# Power_3_3V_to_mc.net
KiCad netlist of a schematic drawn in Altium Designer
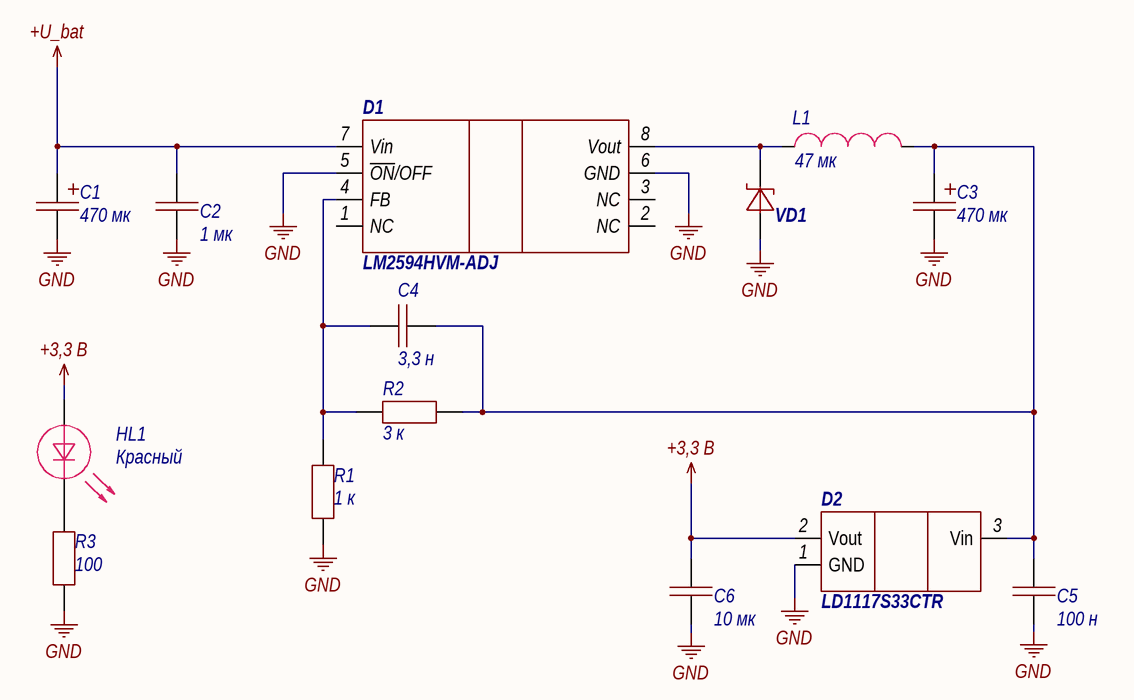
[diagram p0: Power 3.3V to mc.SchDoc]

(export (version "E")
  (design (tool "Eeschema 10.0.6"))
  (components
    (comp (ref "C1")
      (value "470 мк")
      (footprint "RADIAL-2 8mm")
      (description "Конденсатор электролит. 470 мкФ, 50 В, 8 мм")
      (fields (field (name "Comment") "Конденсатор полевой"))
      (libsource (lib "PionerSCHLibrary") (part "Capacitor_pol"))
    )
    (comp (ref "C2")
      (value "1 мк")
      (footprint "0603C")
      (description "Конденсатор керамический SMD, 0603, 1 мкФ")
      (fields (field (name "Comment") "Конденсатор"))
      (libsource (lib "PionerSCHLibrary") (part "Capacitor"))
    )
    (comp (ref "C3")
      (value "470 мк")
      (footprint "RADIAL-2 10MM")
      (description "Конденсатор электролит. 35В, 470мкФ, 10x16")
      (fields (field (name "Comment") "Конденсатор полевой"))
      (libsource (lib "PionerSCHLibrary") (part "Capacitor_pol"))
    )
    (comp (ref "C4")
      (value "3,3 н")
      (footprint "0603C")
      (description "Конденсатор керамический SMD, 0603")
      (fields (field (name "Comment") "Конденсатор"))
      (libsource (lib "PionerSCHLibrary") (part "Capacitor"))
    )
    (comp (ref "C5")
      (value "100 н")
      (footprint "0603C")
      (description "Конденсатор керамический SMD, 0603, 0.1 uF")
      (fields (field (name "Comment") "Конденсатор"))
      (libsource (lib "PionerSCHLibrary") (part "Capacitor"))
    )
    (comp (ref "C6")
      (value "10 мк")
      (footprint "0603C")
      (description "Конденсатор керамический smd 10 мкФ, 0603,")
      (fields (field (name "Comment") "Конденсатор"))
      (libsource (lib "PionerSCHLibrary") (part "Capacitor"))
    )
    (comp (ref "D1")
      (value "LM2594HVM-ADJ")
      (footprint "SOIC_8N")
      (description "Импульсный DC-DC преобразователь, вход до 60 вольт, регулируемый выход, выходной ток 2 Ампера")
      (libsource (lib "PionerSCHLibrary") (part "LM2594HVM-ADJ"))
    )
    (comp (ref "D2")
      (value "LD1117S33CTR")
      (footprint "SOT223")
      (libsource (lib "PionerSCHLibrary") (part "LD1117S33CTR"))
    )
    (comp (ref "HL1")
      (value "~")
      (footprint "0805D")
      (description "Светодиод SMD 0805, 30 мА, 2.1 В")
      (fields (field (name "COLOR") "Красный"))
      (libsource (lib "PionerSCHLibrary") (part "LED"))
    )
    (comp (ref "L1")
      (value "47 мк")
      (footprint "IND_B82477G")
      (description "Катушка индуктивности SMD, 47 мкГн, 2.5 А, 12.8х12.8, B82477G4473M,")
      (fields (field (name "Comment") "Inductance"))
      (libsource (lib "PionerSCHLibrary") (part "Inductance"))
    )
    (comp (ref "R1")
      (value "1 к")
      (footprint "0603R")
      (description "0.1Вт 0603 1 кОм, 1%. Чип резистор (SMD)")
      (fields (field (name "Comment") "Resistor"))
      (libsource (lib "") (part "Resistor_2"))
    )
    (comp (ref "R2")
      (value "3 к")
      (footprint "0603R")
      (description "0.1Вт 0603 1 кОм, 1%, Чип резистор (SMD)")
      (fields (field (name "Comment") "Resistor"))
      (libsource (lib "PionerSCHLibrary") (part "Resistor"))
    )
    (comp (ref "R3")
      (value "100")
      (footprint "0603R")
      (description "Резистор SMD, 43 Ом")
      (fields (field (name "Comment") "Resistor"))
      (libsource (lib "") (part "Resistor_1"))
    )
    (comp (ref "VD1")
      (value "Диод Шоттки")
      (footprint "SMC")
      (description "Диод Шоттки 30 В 3 А, SMD, SMC, SK33")
      (libsource (lib "PionerSCHLibrary") (part "Schottky diode"))
    )
  )
  (nets
    (net (code "1") (name "+3,3 В") (class "Default")
      (node (ref "C6") (pin "2") (pinfunction "2_2") (pintype "passive"))
      (node (ref "D2") (pin "2") (pinfunction "Vout_2") (pintype "passive"))
      (node (ref "HL1") (pin "1") (pinfunction "1_1") (pintype "passive"))
    )
    (net (code "2") (name "+U_bat") (class "Default")
      (node (ref "C1") (pin "1") (pinfunction "1_1") (pintype "passive"))
      (node (ref "C2") (pin "2") (pinfunction "2_2") (pintype "passive"))
      (node (ref "D1") (pin "7") (pinfunction "Vin_7") (pintype "passive"))
    )
    (net (code "3") (name "GND") (class "Default")
      (node (ref "C1") (pin "2") (pinfunction "2_2") (pintype "passive"))
      (node (ref "C2") (pin "1") (pinfunction "1_1") (pintype "passive"))
      (node (ref "C3") (pin "2") (pinfunction "2_2") (pintype "passive"))
      (node (ref "C5") (pin "1") (pinfunction "1_1") (pintype "passive"))
      (node (ref "C6") (pin "1") (pinfunction "1_1") (pintype "passive"))
      (node (ref "D1") (pin "5") (pinfunction "~{ON}/OFF_5") (pintype "passive"))
      (node (ref "D1") (pin "6") (pinfunction "GND_6") (pintype "passive"))
      (node (ref "D2") (pin "1") (pinfunction "GND_1") (pintype "passive"))
      (node (ref "R1") (pin "2") (pinfunction "2_2") (pintype "passive"))
      (node (ref "R3") (pin "1") (pinfunction "1_1") (pintype "passive"))
      (node (ref "VD1") (pin "1") (pinfunction "1_1") (pintype "passive"))
    )
    (net (code "4") (name "Net-(D1-FB)") (class "Default")
      (node (ref "C4") (pin "1") (pinfunction "1_1") (pintype "passive"))
      (node (ref "D1") (pin "4") (pinfunction "FB_4") (pintype "passive"))
      (node (ref "R1") (pin "1") (pinfunction "1_1") (pintype "passive"))
      (node (ref "R2") (pin "1") (pinfunction "1_1") (pintype "passive"))
    )
    (net (code "5") (name "Net-(D1-Vout)") (class "Default")
      (node (ref "D1") (pin "8") (pinfunction "Vout_8") (pintype "passive"))
      (node (ref "L1") (pin "1") (pinfunction "1_1") (pintype "passive"))
      (node (ref "VD1") (pin "2") (pinfunction "2_2") (pintype "passive"))
    )
    (net (code "6") (name "Net-(D2-Vin)") (class "Default")
      (node (ref "C3") (pin "1") (pinfunction "1_1") (pintype "passive"))
      (node (ref "C4") (pin "2") (pinfunction "2_2") (pintype "passive"))
      (node (ref "C5") (pin "2") (pinfunction "2_2") (pintype "passive"))
      (node (ref "D2") (pin "3") (pinfunction "Vin_3") (pintype "passive"))
      (node (ref "L1") (pin "2") (pinfunction "2_2") (pintype "passive"))
      (node (ref "R2") (pin "2") (pinfunction "2_2") (pintype "passive"))
    )
    (net (code "7") (name "Net-(HL1-Pad2)") (class "Default")
      (node (ref "HL1") (pin "2") (pinfunction "2_2") (pintype "passive"))
      (node (ref "R3") (pin "2") (pinfunction "2_2") (pintype "passive"))
    )
    (net (code "8") (name "unconnected-(D1-NC-Pad1)") (class "Default")
      (node (ref "D1") (pin "1") (pinfunction "NC_1") (pintype "passive"))
    )
    (net (code "9") (name "unconnected-(D1-NC-Pad2)") (class "Default")
      (node (ref "D1") (pin "2") (pinfunction "NC_2") (pintype "passive"))
    )
    (net (code "10") (name "unconnected-(D1-NC-Pad3)") (class "Default")
      (node (ref "D1") (pin "3") (pinfunction "NC_3") (pintype "passive"))
    )
  )
)
